# Hat.net
KiCad netlist of a schematic drawn in Altium Designer
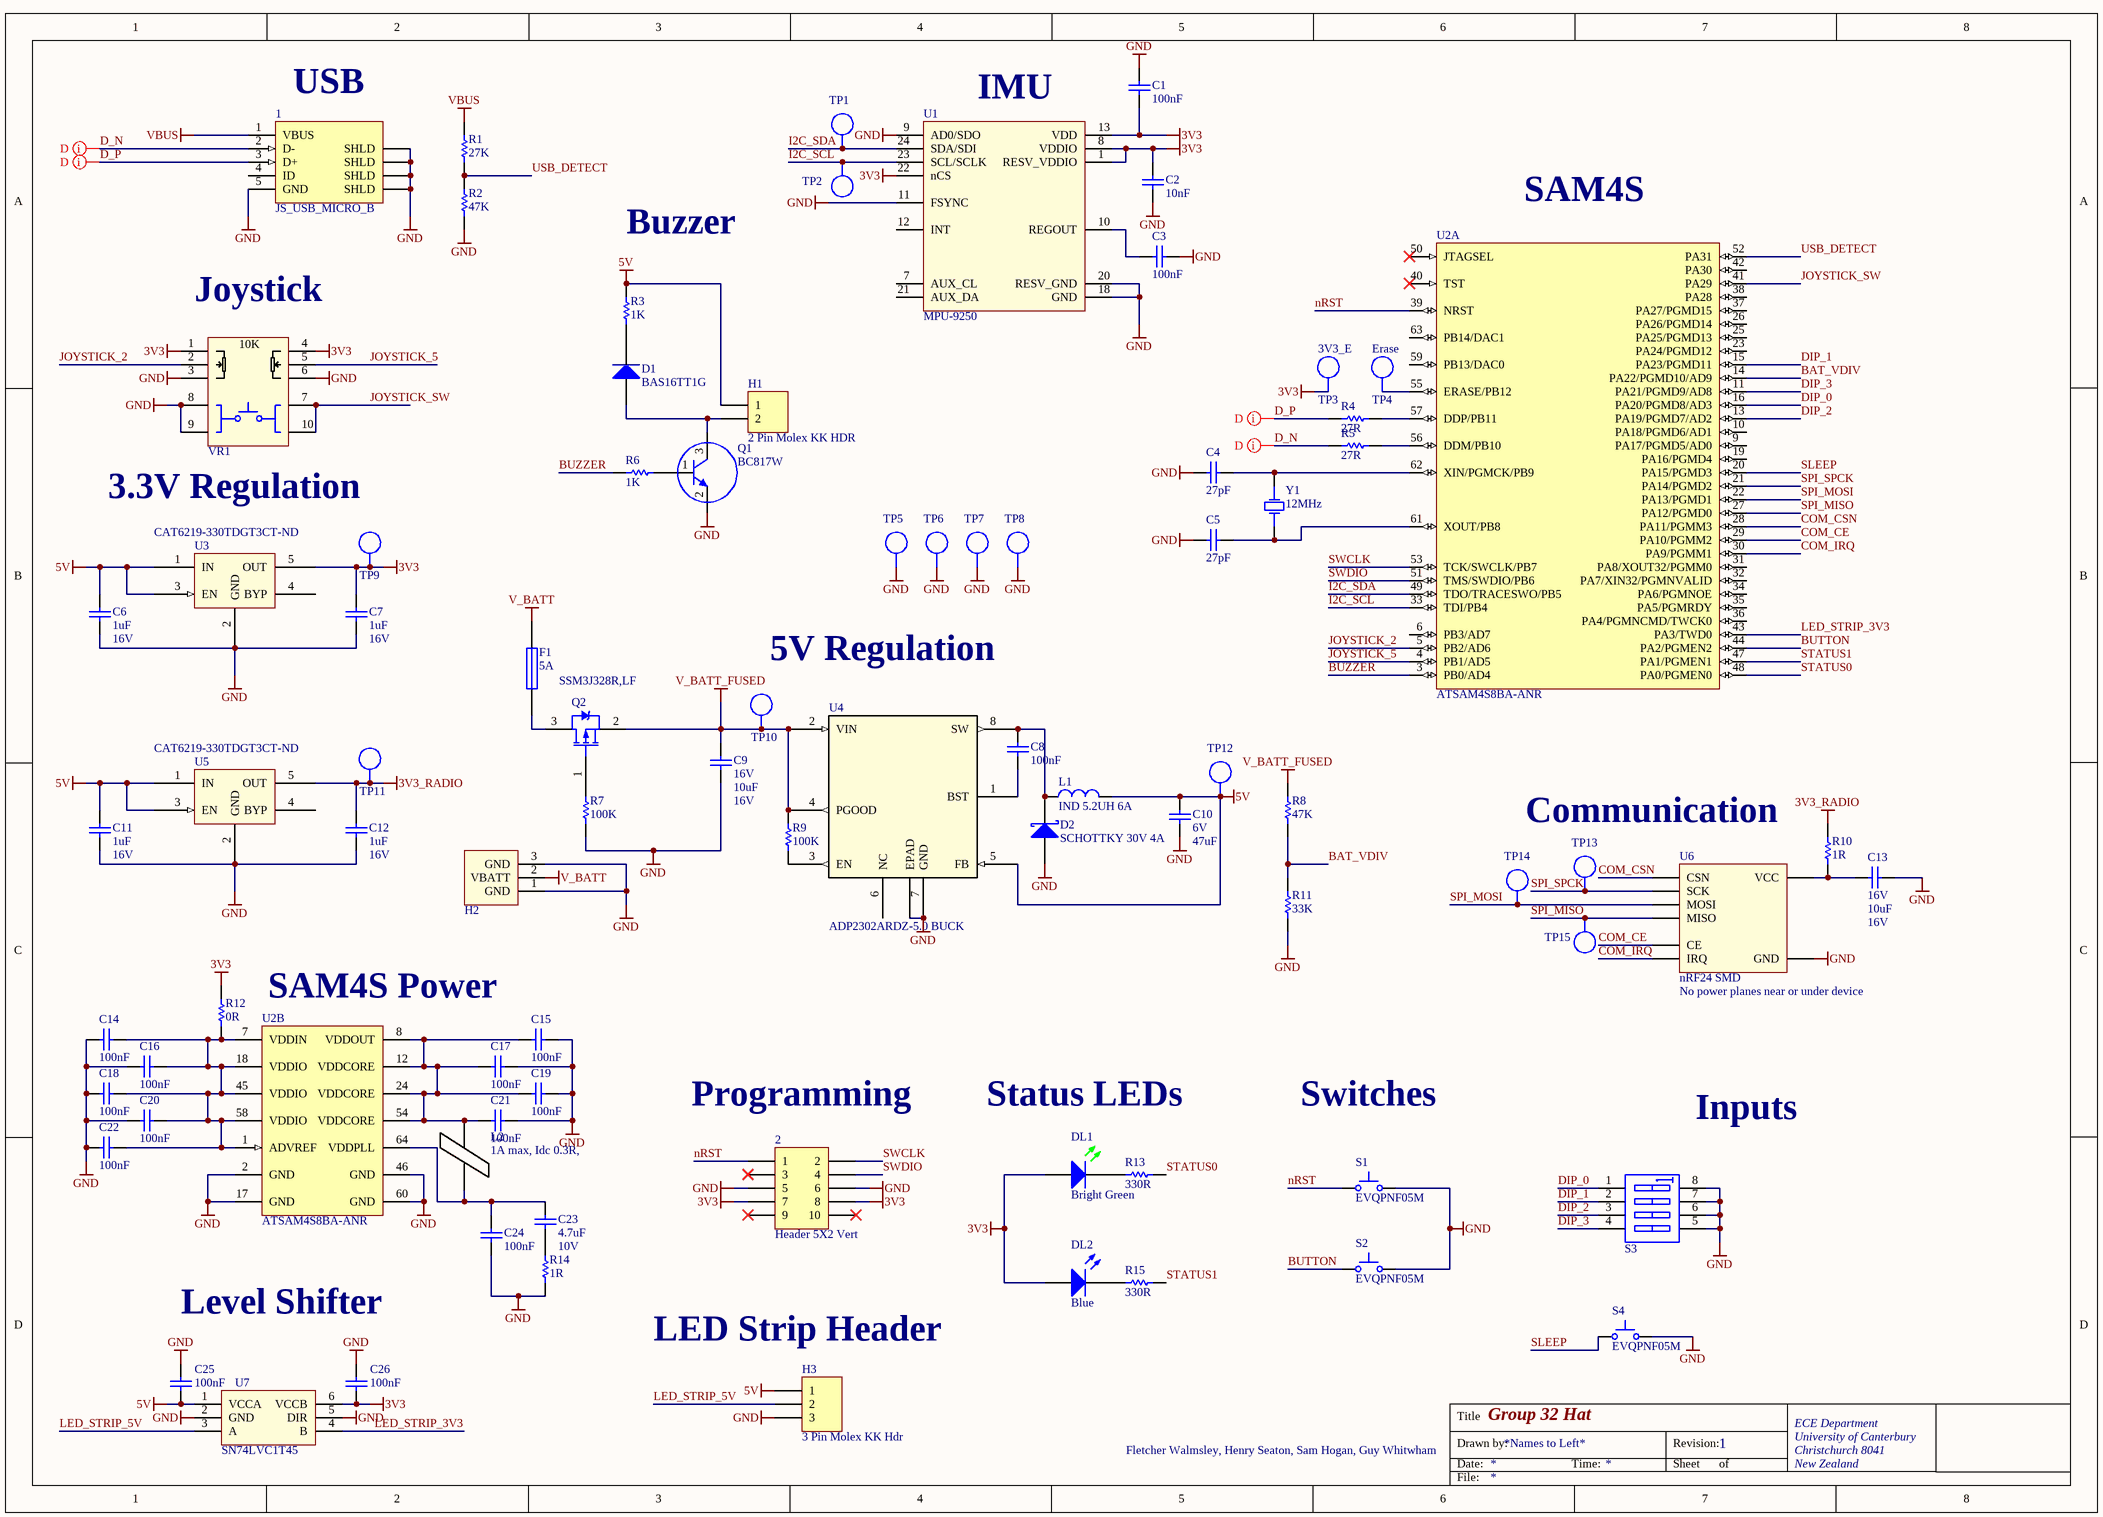
[diagram p0: Hat.SchDoc]

(export (version "E")
  (design (tool "Eeschema 10.0.6"))
  (components
    (comp (ref "1")
      (value "JS_USB_MICRO_B")
      (footprint "FCI_USB_10118194-0001LF")
      (description "CONN USB MICRO B RECPT SMT R/A")
      (fields (field (name "MANUFACTURER") "FCI") (field (name "MANUFACTURER PART NUMBER") "10118194-0001LF"))
      (libsource (lib "ECE AD19Components_19V1") (part "JS_USB_MICRO_B_SMT"))
    )
    (comp (ref "2")
      (value "Header 5X2 Vert")
      (footprint "IDC2.54-V10D")
      (description "IDC Header, 2,54mm, 10-Pin, Vert")
      (libsource (lib "ECE AD19Components_19V1") (part "JA_HDR_IDC_5X2_VERT"))
    )
    (comp (ref "C1")
      (value "100nF")
      (footprint "CAPC1608L")
      (description "CAP CER 100nF X7R +-10% 50V 0603")
      (libsource (lib "ECE AD19Components_19V1") (part "CC_100nF_0603"))
    )
    (comp (ref "C2")
      (value "10nF")
      (footprint "CAPC1608L")
      (description "CAP CER 10nF X7R +-10% 50V 0603")
      (libsource (lib "ECE AD19Components_19V1") (part "CC_10nF_0603"))
    )
    (comp (ref "C3")
      (value "100nF")
      (footprint "CAPC1608L")
      (description "CAP CER 100nF X7R +-10% 50V 0603")
      (libsource (lib "ECE AD19Components_19V1") (part "CC_100nF_0603"))
    )
    (comp (ref "C4")
      (value "27pF")
      (footprint "CAPC1608L")
      (description "CAP CER 27pF NPO/COG +-5% 50V 0603")
      (libsource (lib "ECE AD19Components_19V1") (part "CC_27pF_0603"))
    )
    (comp (ref "C5")
      (value "27pF")
      (footprint "CAPC1608L")
      (description "CAP CER 27pF NPO/COG +-5% 50V 0603")
      (libsource (lib "ECE AD19Components_19V1") (part "CC_27pF_0603"))
    )
    (comp (ref "C6")
      (value "1uF")
      (footprint "CAPC1608L")
      (description "CAP CER 1uF Y5V -20% +80% 16V 0603")
      (fields (field (name "MAX VOLTAGE") "16V"))
      (libsource (lib "ECE AD19Components_19V1") (part "CC_1uF_0603"))
    )
    (comp (ref "C7")
      (value "1uF")
      (footprint "CAPC1608L")
      (description "CAP CER 1uF Y5V -20% +80% 16V 0603")
      (fields (field (name "MAX VOLTAGE") "16V"))
      (libsource (lib "ECE AD19Components_19V1") (part "CC_1uF_0603"))
    )
    (comp (ref "C8")
      (value "100nF")
      (footprint "CAPC1608L")
      (description "CAP CER 100nF X7R +-10% 50V 0603")
      (libsource (lib "ECE AD19Components_19V1") (part "CC_100nF_0603"))
    )
    (comp (ref "C9")
      (value "10uF")
      (footprint "CAPC2012L")
      (description "CAP CER 10uF X5R 16V 0805")
      (fields
        (field (name "MANUFACTURER") "Samsung Electro-Mechanics")
        (field (name "MANUFACTURER PART NUMBER") "CL21A106KOQNNWE")
        (field (name "VOLTAGE - RATED") "16V")
        (field (name "MAX VOLTAGE") "16V")
      )
      (libsource (lib "ENCE461AD19_19V2") (part "CC_10uF_16V_0805"))
    )
    (comp (ref "C10")
      (value "47uF")
      (footprint "CAPC3216L")
      (description "CAP CER 47uF X5R -/+20% 6V 1206")
      (fields (field (name "MAX VOLTAGE") "6V"))
      (libsource (lib "ECE AD19Components_19V1") (part "CC_47uF_1206"))
    )
    (comp (ref "C11")
      (value "1uF")
      (footprint "CAPC1608L")
      (description "CAP CER 1uF Y5V -20% +80% 16V 0603")
      (fields (field (name "MAX VOLTAGE") "16V"))
      (libsource (lib "ECE AD19Components_19V1") (part "CC_1uF_0603"))
    )
    (comp (ref "C12")
      (value "1uF")
      (footprint "CAPC1608L")
      (description "CAP CER 1uF Y5V -20% +80% 16V 0603")
      (fields (field (name "MAX VOLTAGE") "16V"))
      (libsource (lib "ECE AD19Components_19V1") (part "CC_1uF_0603"))
    )
    (comp (ref "C13")
      (value "10uF")
      (footprint "CAPC2012L")
      (description "CAP CER 10uF X5R 16V 0805")
      (fields
        (field (name "MANUFACTURER") "Samsung Electro-Mechanics")
        (field (name "MANUFACTURER PART NUMBER") "CL21A106KOQNNWE")
        (field (name "VOLTAGE - RATED") "16V")
        (field (name "MAX VOLTAGE") "16V")
      )
      (libsource (lib "ENCE461AD19_19V2") (part "CC_10uF_16V_0805"))
    )
    (comp (ref "C14")
      (value "100nF")
      (footprint "CAPC1608L")
      (description "CAP CER 100nF X7R +-10% 50V 0603")
      (libsource (lib "ECE AD19Components_19V1") (part "CC_100nF_0603"))
    )
    (comp (ref "C15")
      (value "100nF")
      (footprint "CAPC1608L")
      (description "CAP CER 100nF X7R +-10% 50V 0603")
      (libsource (lib "ECE AD19Components_19V1") (part "CC_100nF_0603"))
    )
    (comp (ref "C16")
      (value "100nF")
      (footprint "CAPC1608L")
      (description "CAP CER 100nF X7R +-10% 50V 0603")
      (libsource (lib "ECE AD19Components_19V1") (part "CC_100nF_0603"))
    )
    (comp (ref "C17")
      (value "100nF")
      (footprint "CAPC1608L")
      (description "CAP CER 100nF X7R +-10% 50V 0603")
      (libsource (lib "ECE AD19Components_19V1") (part "CC_100nF_0603"))
    )
    (comp (ref "C18")
      (value "100nF")
      (footprint "CAPC1608L")
      (description "CAP CER 100nF X7R +-10% 50V 0603")
      (libsource (lib "ECE AD19Components_19V1") (part "CC_100nF_0603"))
    )
    (comp (ref "C19")
      (value "100nF")
      (footprint "CAPC1608L")
      (description "CAP CER 100nF X7R +-10% 50V 0603")
      (libsource (lib "ECE AD19Components_19V1") (part "CC_100nF_0603"))
    )
    (comp (ref "C20")
      (value "100nF")
      (footprint "CAPC1608L")
      (description "CAP CER 100nF X7R +-10% 50V 0603")
      (libsource (lib "ECE AD19Components_19V1") (part "CC_100nF_0603"))
    )
    (comp (ref "C21")
      (value "100nF")
      (footprint "CAPC1608L")
      (description "CAP CER 100nF X7R +-10% 50V 0603")
      (libsource (lib "ECE AD19Components_19V1") (part "CC_100nF_0603"))
    )
    (comp (ref "C22")
      (value "100nF")
      (footprint "CAPC1608L")
      (description "CAP CER 100nF X7R +-10% 50V 0603")
      (libsource (lib "ECE AD19Components_19V1") (part "CC_100nF_0603"))
    )
    (comp (ref "C23")
      (value "4.7uF")
      (footprint "CAPC1608N")
      (description "CAP CER 4.7uF X5R +-20%  10V 0603")
      (fields (field (name "MAX VOLTAGE") "10V"))
      (libsource (lib "ECE AD19Components_19V1") (part "CC_4.7uF_0603"))
    )
    (comp (ref "C24")
      (value "100nF")
      (footprint "CAPC1608L")
      (description "CAP CER 100nF X7R +-10% 50V 0603")
      (libsource (lib "ECE AD19Components_19V1") (part "CC_100nF_0603"))
    )
    (comp (ref "C25")
      (value "100nF")
      (footprint "CAPC1608L")
      (description "CAP CER 100nF X7R +-10% 50V 0603")
      (libsource (lib "ECE AD19Components_19V1") (part "CC_100nF_0603"))
    )
    (comp (ref "C26")
      (value "100nF")
      (footprint "CAPC1608L")
      (description "CAP CER 100nF X7R +-10% 50V 0603")
      (libsource (lib "ECE AD19Components_19V1") (part "CC_100nF_0603"))
    )
    (comp (ref "D1")
      (value "BAS16TT1G")
      (footprint "SOT416")
      (description "Diode Switching, Vr 75V, 200mA, SOT-416")
      (fields (field (name "MANUFACTURER") "ON Semiconductor"))
      (libsource (lib "ECE AD19Components_19V1") (part "DR_BAS16TT1G"))
    )
    (comp (ref "D2")
      (value "SCHOTTKY 30V 4A")
      (footprint "SMC")
      (description "DIODE SCHOTTKY 30V 4A SMC")
      (fields
        (field (name "MANUFACTURER") "ON Semiconductor")
        (field (name "MANUFACTURER PART NUMBER") "MBRS330T3G")
      )
      (libsource (lib "ENCE461AD19_19V2") (part "MBRS330T3G"))
    )
    (comp (ref "DL1")
      (value "Bright Green")
      (footprint "WL-SMCW0603")
      (description "LED Bright Green 40mcd 0603 SMD")
      (fields
        (field (name "MANUFACTURER") "WURTH ELEKTRONIK")
        (field (name "MANUFACTURER PART NUMBER") "150060VS75000")
        (field (name "LED COLOUR") "Bright Green")
      )
      (libsource (lib "ECE AD19Components_19V1") (part "DL_150060VS75000"))
    )
    (comp (ref "DL2")
      (value "Blue")
      (footprint "WL-SMCW0603")
      (description "LED Blue 270mcd 0603 SMD")
      (fields
        (field (name "MANUFACTURER") "WURTH ELEKTRONIK")
        (field (name "MANUFACTURER PART NUMBER") "150060BS75000")
        (field (name "LED COLOUR") "Blue")
      )
      (libsource (lib "ECE AD19Components_19V1") (part "DL_150060BS75000"))
    )
    (comp (ref "F1")
      (value "5A")
      (footprint "RESC3216N")
      (description "Fuse 5.0A Fast Acting 1206 SMD")
      (fields (field (name "MANUFACTURER PART NUMBER") "C1F5") (field (name "MANUFACTURER") "Bel TRP"))
      (libsource (lib "ECE AD19Components_19V1") (part "FS_Fuse_5.0A"))
    )
    (comp (ref "H1")
      (value "2 Pin Molex KK HDR")
      (footprint "MOLEX_KK_2_HDR")
      (description "CONN HEADER 2POS 2.54mm VERT_Thru Hole")
      (libsource (lib "ECE AD19Components_19V1") (part "JA_MOLEX_KK_2POS"))
    )
    (comp (ref "H2")
      (value "Battery_HEADER_3pin")
      (footprint "BATT_HEADER_3POS")
      (description "3Pin Header 2.54mm spacing")
      (libsource (lib "ENCE461AD19_19V2") (part "Battery_HEADER_3pin"))
    )
    (comp (ref "H3")
      (value "3 Pin Molex KK Hdr")
      (footprint "MOLEX_KK_3_HDR")
      (description "CONN HEADER 3POS 2.54mm VERT_Thru Hole")
      (fields (field (name "MANUFACTURER") "Molex"))
      (libsource (lib "ECE AD19Components_19V1") (part "JA_MOLEX_KK_3POS"))
    )
    (comp (ref "L1")
      (value "IND 5.2UH 6A")
      (footprint "INDUCTOR5u2")
      (description "FIXED IND 5.2UH 6A 22 MOHM SMD")
      (fields
        (field (name "MANUFACTURER") "Sumida America Components Inc.")
        (field (name "MANUFACTURER PART NUMBER") "CDRH104RNP-5R2NC")
      )
      (libsource (lib "ENCE461AD19_19V2") (part "CDRH104RNP-5R2NC"))
    )
    (comp (ref "L2")
      (value "1A max, Idc 0.3R,")
      (footprint "INDC3216L")
      (description "Ferrite Bead, Rdc 0.3R, Z100MHZ 600R, Imax 1A, SMD 1206")
      (fields
        (field (name "MANUFACTURER") "FAIR-RITE")
        (field (name "MANUFACTURER PART NUMBER") "2512066017Y1")
      )
      (libsource (lib "ECE AD19Components_19V1") (part "IN_Ferrite-Bead"))
    )
    (comp (ref "Q1")
      (value "BC817W")
      (footprint "SOT323_M")
      (description "NPN GP Bipolar Transistor 45V 500mA SOT323")
      (fields (field (name "MANUFACTURER") "NXP"))
      (libsource (lib "ECE AD19Components_19V1") (part "TB_BC817W"))
    )
    (comp (ref "Q2")
      (value "SSM3J328R,LF")
      (footprint "SOT23_L")
      (description "MOSFET P-CH 20V 6A SOT23-3")
      (fields
        (field (name "MANUFACTURER") "Toshiba")
        (field (name "MANUFACTURER PART NUMBER") "SSM3J328R,LF")
      )
      (libsource (lib "ECE AD19Components_19V1") (part "TM_SSM3J328R"))
    )
    (comp (ref "R1")
      (value "27K")
      (footprint "RESC1608L")
      (description "RES 27K OHM 1/10W 5% 0603 SMD")
      (libsource (lib "ECE AD19Components_19V1") (part "RS_27K"))
    )
    (comp (ref "R2")
      (value "47K")
      (footprint "RESC1608N")
      (description "RES 47.0K OHM 1/10W 5% 0603 SMD")
      (libsource (lib "ECE AD19Components_19V1") (part "RS_47K"))
    )
    (comp (ref "R3")
      (value "1K")
      (footprint "RESC1608L")
      (description "RES 1.0K OHM 1/10W 5% 0603 SMD")
      (libsource (lib "ECE AD19Components_19V1") (part "RS_1K"))
    )
    (comp (ref "R4")
      (value "27R")
      (footprint "RESC1608L")
      (description "RES 27 OHM 1/10W 5% 0603 SMD")
      (libsource (lib "ECE AD19Components_19V1") (part "RS_27R"))
    )
    (comp (ref "R5")
      (value "27R")
      (footprint "RESC1608L")
      (description "RES 27 OHM 1/10W 5% 0603 SMD")
      (libsource (lib "ECE AD19Components_19V1") (part "RS_27R"))
    )
    (comp (ref "R6")
      (value "1K")
      (footprint "RESC1608L")
      (description "RES 1.0K OHM 1/10W 5% 0603 SMD")
      (libsource (lib "ECE AD19Components_19V1") (part "RS_1K"))
    )
    (comp (ref "R7")
      (value "100K")
      (footprint "RESC1608L")
      (description "RES 100K OHM 1/10W 5% 0603 SMD")
      (libsource (lib "ECE AD19Components_19V1") (part "RS_100K"))
    )
    (comp (ref "R8")
      (value "47K")
      (footprint "RESC1608N")
      (description "RES 47.0K OHM 1/10W 5% 0603 SMD")
      (libsource (lib "ECE AD19Components_19V1") (part "RS_47K"))
    )
    (comp (ref "R9")
      (value "100K")
      (footprint "RESC1608L")
      (description "RES 100K OHM 1/10W 5% 0603 SMD")
      (libsource (lib "ECE AD19Components_19V1") (part "RS_100K"))
    )
    (comp (ref "R10")
      (value "1R")
      (footprint "RESC3216L")
      (description "RES 1R OHM 1/4W 5% 1206 SMD")
      (libsource (lib "ECE AD19Components_19V1") (part "RT_1R"))
    )
    (comp (ref "R11")
      (value "33K")
      (footprint "RESC1608L")
      (description "RES 33.0K OHM 1/10W 5% 0603 SMD")
      (libsource (lib "ECE AD19Components_19V1") (part "RS_33K"))
    )
    (comp (ref "R12")
      (value "0R")
      (footprint "RESC1608L")
      (description "RES 0.0 OHM 1/10W 5% 0603 SMD")
      (libsource (lib "ECE AD19Components_19V1") (part "RS_0R0"))
    )
    (comp (ref "R13")
      (value "330R")
      (footprint "RESC1608L")
      (description "RES 330 OHM 1/10W 5% 0603 SMD")
      (libsource (lib "ECE AD19Components_19V1") (part "RS_330R"))
    )
    (comp (ref "R14")
      (value "1R")
      (footprint "RESC3216L")
      (description "RES 1R OHM 1/4W 5% 1206 SMD")
      (libsource (lib "ECE AD19Components_19V1") (part "RT_1R"))
    )
    (comp (ref "R15")
      (value "330R")
      (footprint "RESC1608L")
      (description "RES 330 OHM 1/10W 5% 0603 SMD")
      (libsource (lib "ECE AD19Components_19V1") (part "RS_330R"))
    )
    (comp (ref "S1")
      (value "EVQPNF05M")
      (footprint "EVQPNF05M")
      (description "Panasonic 6 x 3.5mm SMD Light Touch Switch Type SMD")
      (fields (field (name "MANUFACTURER") "Panasonic"))
      (libsource (lib "ENCE461_extras_2020") (part "WS_EVQPNF05M"))
    )
    (comp (ref "S2")
      (value "EVQPNF05M")
      (footprint "EVQPNF05M")
      (description "Panasonic 6 x 3.5mm SMD Light Touch Switch Type SMD")
      (fields (field (name "MANUFACTURER") "Panasonic"))
      (libsource (lib "ECE AD19Components_19V1") (part "WS_EVQPNF05M"))
    )
    (comp (ref "S3")
      (value "WS_SW DIP-4")
      (footprint "DIP_SW_4WAY_SMD -")
      (description "DIP Switch, 4 Position, SPST SMD")
      (fields
        (field (name "MANUFACTURER") "OMRON ELECTRONIC COMPONENTS")
        (field (name "MANUFACTURER PART NUMBER") "A6SN-4101")
      )
      (libsource (lib "ECE AD19Components_19V1") (part "WS_SW DIP-4"))
    )
    (comp (ref "S4")
      (value "EVQPNF05M")
      (footprint "EVQPNF05M")
      (description "Panasonic 6 x 3.5mm SMD Light Touch Switch Type SMD")
      (fields (field (name "MANUFACTURER") "Panasonic"))
      (libsource (lib "ECE AD19Components_19V1") (part "WS_EVQPNF05M"))
    )
    (comp (ref "TP1")
      (value "SDA")
      (footprint "TP_1206")
      (description "Test-Point 3.3x1.6x2.1mm SMD")
      (fields
        (field (name "MANUFACTURER") "Harwin Inc")
        (field (name "MANUFACTURER PART NUMBER") "S1751-46R")
      )
      (libsource (lib "ECE AD19Components_19V1") (part "TP_1206"))
    )
    (comp (ref "TP2")
      (value "SCK")
      (footprint "TP_1206")
      (description "Test-Point 3.3x1.6x2.1mm SMD")
      (fields
        (field (name "MANUFACTURER") "Harwin Inc")
        (field (name "MANUFACTURER PART NUMBER") "S1751-46R")
      )
      (libsource (lib "ECE AD19Components_19V1") (part "TP_1206"))
    )
    (comp (ref "TP3")
      (value "3V3_E")
      (footprint "TP_1206")
      (description "Test-Point 3.3x1.6x2.1mm SMD")
      (fields
        (field (name "MANUFACTURER") "Harwin Inc")
        (field (name "MANUFACTURER PART NUMBER") "S1751-46R")
      )
      (libsource (lib "ECE AD19Components_19V1") (part "TP_1206"))
    )
    (comp (ref "TP4")
      (value "Erase")
      (footprint "TP_1206")
      (description "Test-Point 3.3x1.6x2.1mm SMD")
      (fields
        (field (name "MANUFACTURER") "Harwin Inc")
        (field (name "MANUFACTURER PART NUMBER") "S1751-46R")
      )
      (libsource (lib "ECE AD19Components_19V1") (part "TP_1206"))
    )
    (comp (ref "TP5")
      (value "GND")
      (footprint "TP_1206")
      (description "Test-Point 3.3x1.6x2.1mm SMD")
      (fields
        (field (name "MANUFACTURER") "Harwin Inc")
        (field (name "MANUFACTURER PART NUMBER") "S1751-46R")
      )
      (libsource (lib "ECE AD19Components_19V1") (part "TP_1206"))
    )
    (comp (ref "TP6")
      (value "GND")
      (footprint "TP_1206")
      (description "Test-Point 3.3x1.6x2.1mm SMD")
      (fields
        (field (name "MANUFACTURER") "Harwin Inc")
        (field (name "MANUFACTURER PART NUMBER") "S1751-46R")
      )
      (libsource (lib "ECE AD19Components_19V1") (part "TP_1206"))
    )
    (comp (ref "TP7")
      (value "GND")
      (footprint "TP_1206")
      (description "Test-Point 3.3x1.6x2.1mm SMD")
      (fields
        (field (name "MANUFACTURER") "Harwin Inc")
        (field (name "MANUFACTURER PART NUMBER") "S1751-46R")
      )
      (libsource (lib "ECE AD19Components_19V1") (part "TP_1206"))
    )
    (comp (ref "TP8")
      (value "GND")
      (footprint "TP_1206")
      (description "Test-Point 3.3x1.6x2.1mm SMD")
      (fields
        (field (name "MANUFACTURER") "Harwin Inc")
        (field (name "MANUFACTURER PART NUMBER") "S1751-46R")
      )
      (libsource (lib "ECE AD19Components_19V1") (part "TP_1206"))
    )
    (comp (ref "TP9")
      (value "3V3")
      (footprint "TP_1206")
      (description "Test-Point 3.3x1.6x2.1mm SMD")
      (fields
        (field (name "MANUFACTURER") "Harwin Inc")
        (field (name "MANUFACTURER PART NUMBER") "S1751-46R")
      )
      (libsource (lib "ECE AD19Components_19V1") (part "TP_1206"))
    )
    (comp (ref "TP10")
      (value "V_BATT")
      (footprint "TP_1206")
      (description "Test-Point 3.3x1.6x2.1mm SMD")
      (fields
        (field (name "MANUFACTURER") "Harwin Inc")
        (field (name "MANUFACTURER PART NUMBER") "S1751-46R")
      )
      (libsource (lib "ECE AD19Components_19V1") (part "TP_1206"))
    )
    (comp (ref "TP11")
      (value "3V3_R")
      (footprint "TP_1206")
      (description "Test-Point 3.3x1.6x2.1mm SMD")
      (fields
        (field (name "MANUFACTURER") "Harwin Inc")
        (field (name "MANUFACTURER PART NUMBER") "S1751-46R")
      )
      (libsource (lib "ECE AD19Components_19V1") (part "TP_1206"))
    )
    (comp (ref "TP12")
      (value "5V")
      (footprint "TP_1206")
      (description "Test-Point 3.3x1.6x2.1mm SMD")
      (fields
        (field (name "MANUFACTURER") "Harwin Inc")
        (field (name "MANUFACTURER PART NUMBER") "S1751-46R")
      )
      (libsource (lib "ECE AD19Components_19V1") (part "TP_1206"))
    )
    (comp (ref "TP13")
      (value "SPCK")
      (footprint "TP_1206")
      (description "Test-Point 3.3x1.6x2.1mm SMD")
      (fields
        (field (name "MANUFACTURER") "Harwin Inc")
        (field (name "MANUFACTURER PART NUMBER") "S1751-46R")
      )
      (libsource (lib "ECE AD19Components_19V1") (part "TP_1206"))
    )
    (comp (ref "TP14")
      (value "MOSI")
      (footprint "TP_1206")
      (description "Test-Point 3.3x1.6x2.1mm SMD")
      (fields
        (field (name "MANUFACTURER") "Harwin Inc")
        (field (name "MANUFACTURER PART NUMBER") "S1751-46R")
      )
      (libsource (lib "ECE AD19Components_19V1") (part "TP_1206"))
    )
    (comp (ref "TP15")
      (value "MISO")
      (footprint "TP_1206")
      (description "Test-Point 3.3x1.6x2.1mm SMD")
      (fields
        (field (name "MANUFACTURER") "Harwin Inc")
        (field (name "MANUFACTURER PART NUMBER") "S1751-46R")
      )
      (libsource (lib "ECE AD19Components_19V1") (part "TP_1206"))
    )
    (comp (ref "U1")
      (value "MPU-9250")
      (footprint "Quad24")
      (description "9 axis IMU")
      (libsource (lib "ENCE461AD19_19V2") (part "MPU-9250"))
    )
    (comp (ref "U2")
      (value "ATSAM4S8BA-ANR")
      (footprint "LQFP64_L")
      (description "IC MCU 32BIT 512KB FLASH 64LQFP")
      (fields (field (name "MANUFACTURER") "Atmel"))
      (libsource (lib "ECE AD19Components_19V1") (part "SE_ATSAM4S16BA-MU"))
    )
    (comp (ref "U3")
      (value "CAT6219-330TDGT3")
      (footprint "SOT95P280X145-5N")
      (description "IC REG LIN 3.3V 500MA TSOT23-5")
      (fields
        (field (name "BASE PART NUMBER") "CAT6219")
        (field (name "SUPPLIER PART NUMBER") "CAT6219-330TDGT3CT-ND")
      )
      (libsource (lib "ENCE461AD19_19V2") (part "SV_CAT6219-330TDGT3"))
    )
    (comp (ref "U4")
      (value "ADP2302ARDZ-5.0 BUCK")
      (footprint "RD_8_1")
      (description "IC REG BUCK 5V 2A 8SOIC")
      (fields (field (name "MANUFACTURER_PART_NUMBER") "ADP2302ARDZ-5.0-R7"))
      (libsource (lib "ENCE461AD19_19V2") (part "ADP2302ARDZ-5.0-R7"))
    )
    (comp (ref "U5")
      (value "CAT6219-330TDGT3")
      (footprint "SOT95P280X145-5N")
      (description "IC REG LIN 3.3V 500MA TSOT23-5")
      (fields
        (field (name "BASE PART NUMBER") "CAT6219")
        (field (name "SUPPLIER PART NUMBER") "CAT6219-330TDGT3CT-ND")
      )
      (libsource (lib "ENCE461AD19_19V2") (part "SV_CAT6219-330TDGT3"))
    )
    (comp (ref "U6")
      (value "nRF24 SMD")
      (footprint "NRF24")
      (description "nRF24 SMD Module")
      (fields (field (name "WARNING") "No power planes near or under device"))
      (libsource (lib "ENCE461AD19_19V2") (part "NRF24"))
    )
    (comp (ref "U7")
      (value "SN74LVC1T45")
      (footprint "SOT23-6_N")
      (description "1.8V - 5V level converter")
      (libsource (lib "ENCE461_extras_2020") (part "SN74LVC1T45"))
    )
    (comp (ref "VR1")
      (value "Joystick 10k with Sw")
      (footprint "Joystick_Sw")
      (description "JOYSTICK 10K OHM 2 AXIS TH")
      (libsource (lib "ENCE461AD19_19V2") (part "Joystick 10k with Sw"))
    )
    (comp (ref "Y1")
      (value "12MHz")
      (footprint "6.0X3.5-4")
      (description "CRYSTAL 12MHZ 18PF 6X3.5mm SMD")
      (fields
        (field (name "MANUFACTURER") "CTS-Frequency Controls")
        (field (name "MANUFACTURER PART NUMBER") "406C35D12M00000")
        (field (name "FREQUENCY") "12MHz")
      )
      (libsource (lib "ECE AD19Components_19V1") (part "XT_CRYSTAL_12MHz_18pF"))
    )
  )
  (nets
    (net (code "1") (name "/BAT_VDIV") (class "Default")
      (node (ref "R11") (pin "1") (pinfunction "1_1") (pintype "passive"))
      (node (ref "R8") (pin "2") (pinfunction "2_2") (pintype "passive"))
      (node (ref "U2") (pin "14") (pinfunction "PA22/PGMD10/AD9_14") (pintype "bidirectional"))
    )
    (net (code "2") (name "/BUTTON") (class "Default")
      (node (ref "S2") (pin "1") (pintype "passive"))
      (node (ref "U2") (pin "44") (pinfunction "PA2/PGMEN2_44") (pintype "bidirectional"))
    )
    (net (code "3") (name "/BUZZER") (class "Default")
      (node (ref "R6") (pin "2") (pinfunction "2_2") (pintype "passive"))
      (node (ref "U2") (pin "3") (pinfunction "PB0/AD4_3") (pintype "bidirectional"))
    )
    (net (code "4") (name "/COM_CE") (class "Default")
      (node (ref "U2") (pin "29") (pinfunction "PA10/PGMM2_29") (pintype "bidirectional"))
      (node (ref "U6") (pin "3") (pinfunction "CE_3") (pintype "passive"))
    )
    (net (code "5") (name "/COM_CSN") (class "Default")
      (node (ref "U2") (pin "28") (pinfunction "PA11/PGMM3_28") (pintype "bidirectional"))
      (node (ref "U6") (pin "4") (pinfunction "CSN_4") (pintype "passive"))
    )
    (net (code "6") (name "/COM_IRQ") (class "Default")
      (node (ref "U2") (pin "30") (pinfunction "PA9/PGMM1_30") (pintype "bidirectional"))
      (node (ref "U6") (pin "8") (pinfunction "IRQ_8") (pintype "passive"))
    )
    (net (code "7") (name "/DIP_0") (class "Default")
      (node (ref "S3") (pin "1") (pinfunction "A1_1") (pintype "passive"))
      (node (ref "U2") (pin "16") (pinfunction "PA20/PGMD8/AD3_16") (pintype "bidirectional"))
    )
    (net (code "8") (name "/DIP_1") (class "Default")
      (node (ref "S3") (pin "2") (pinfunction "A2_2") (pintype "passive"))
      (node (ref "U2") (pin "15") (pinfunction "PA23/PGMD11_15") (pintype "bidirectional"))
    )
    (net (code "9") (name "/DIP_2") (class "Default")
      (node (ref "S3") (pin "3") (pinfunction "A3_3") (pintype "passive"))
      (node (ref "U2") (pin "13") (pinfunction "PA19/PGMD7/AD2_13") (pintype "bidirectional"))
    )
    (net (code "10") (name "/DIP_3") (class "Default")
      (node (ref "S3") (pin "4") (pinfunction "A4_4") (pintype "passive"))
      (node (ref "U2") (pin "11") (pinfunction "PA21/PGMD9/AD8_11") (pintype "bidirectional"))
    )
    (net (code "11") (name "/D_N") (class "Default")
      (node (ref "1") (pin "2") (pinfunction "D-_2") (pintype "input"))
      (node (ref "R5") (pin "1") (pinfunction "1_1") (pintype "passive"))
    )
    (net (code "12") (name "/D_P") (class "Default")
      (node (ref "1") (pin "3") (pinfunction "D+_3") (pintype "input"))
      (node (ref "R4") (pin "1") (pinfunction "1_1") (pintype "passive"))
    )
    (net (code "13") (name "/I2C_SCL") (class "Default")
      (node (ref "TP2") (pin "1") (pinfunction "1_1") (pintype "passive"))
      (node (ref "U1") (pin "23") (pinfunction "SCL/SCLK_23") (pintype "passive"))
      (node (ref "U2") (pin "33") (pinfunction "TDI/PB4_33") (pintype "bidirectional"))
    )
    (net (code "14") (name "/I2C_SDA") (class "Default")
      (node (ref "TP1") (pin "1") (pinfunction "1_1") (pintype "passive"))
      (node (ref "U1") (pin "24") (pinfunction "SDA/SDI_24") (pintype "passive"))
      (node (ref "U2") (pin "49") (pinfunction "TDO/TRACESWO/PB5_49") (pintype "bidirectional"))
    )
    (net (code "15") (name "/JOYSTICK_2") (class "Default")
      (node (ref "U2") (pin "5") (pinfunction "PB2/AD6_5") (pintype "bidirectional"))
      (node (ref "VR1") (pin "2") (pinfunction "2_2") (pintype "passive"))
    )
    (net (code "16") (name "/JOYSTICK_5") (class "Default")
      (node (ref "U2") (pin "4") (pinfunction "PB1/AD5_4") (pintype "bidirectional"))
      (node (ref "VR1") (pin "5") (pinfunction "2'_5") (pintype "passive"))
    )
    (net (code "17") (name "/JOYSTICK_SW") (class "Default")
      (node (ref "U2") (pin "41") (pinfunction "PA29_41") (pintype "bidirectional"))
      (node (ref "VR1") (pin "10") (pinfunction "10_10") (pintype "passive"))
      (node (ref "VR1") (pin "7") (pinfunction "7_7") (pintype "passive"))
    )
    (net (code "18") (name "/LED_STRIP_3V3") (class "Default")
      (node (ref "U2") (pin "43") (pinfunction "PA3/TWD0_43") (pintype "bidirectional"))
      (node (ref "U7") (pin "4") (pinfunction "B_4") (pintype "passive"))
    )
    (net (code "19") (name "/LED_STRIP_5V") (class "Default")
      (node (ref "H3") (pin "2") (pinfunction "2_2") (pintype "passive"))
      (node (ref "U7") (pin "3") (pinfunction "A_3") (pintype "passive"))
    )
    (net (code "20") (name "/SLEEP") (class "Default")
      (node (ref "S4") (pin "1") (pintype "passive"))
      (node (ref "U2") (pin "20") (pinfunction "PA15/PGMD3_20") (pintype "bidirectional"))
    )
    (net (code "21") (name "/SPI_MISO") (class "Default")
      (node (ref "TP15") (pin "1") (pinfunction "1_1") (pintype "passive"))
      (node (ref "U2") (pin "27") (pinfunction "PA12/PGMD0_27") (pintype "bidirectional"))
      (node (ref "U6") (pin "7") (pinfunction "MISO_7") (pintype "passive"))
    )
    (net (code "22") (name "/SPI_MOSI") (class "Default")
      (node (ref "TP14") (pin "1") (pinfunction "1_1") (pintype "passive"))
      (node (ref "U2") (pin "22") (pinfunction "PA13/PGMD1_22") (pintype "bidirectional"))
      (node (ref "U6") (pin "6") (pinfunction "MOSI_6") (pintype "passive"))
    )
    (net (code "23") (name "/SPI_SPCK") (class "Default")
      (node (ref "TP13") (pin "1") (pinfunction "1_1") (pintype "passive"))
      (node (ref "U2") (pin "21") (pinfunction "PA14/PGMD2_21") (pintype "bidirectional"))
      (node (ref "U6") (pin "5") (pinfunction "SCK_5") (pintype "passive"))
    )
    (net (code "24") (name "/STATUS0") (class "Default")
      (node (ref "R13") (pin "2") (pinfunction "2_2") (pintype "passive"))
      (node (ref "U2") (pin "48") (pinfunction "PA0/PGMEN0_48") (pintype "bidirectional"))
    )
    (net (code "25") (name "/STATUS1") (class "Default")
      (node (ref "R15") (pin "2") (pinfunction "2_2") (pintype "passive"))
      (node (ref "U2") (pin "47") (pinfunction "PA1/PGMEN1_47") (pintype "bidirectional"))
    )
    (net (code "26") (name "/SWCLK") (class "Default")
      (node (ref "2") (pin "2") (pinfunction "2_2") (pintype "passive"))
      (node (ref "U2") (pin "53") (pinfunction "TCK/SWCLK/PB7_53") (pintype "bidirectional"))
    )
    (net (code "27") (name "/SWDIO") (class "Default")
      (node (ref "2") (pin "4") (pinfunction "4_4") (pintype "passive"))
      (node (ref "U2") (pin "51") (pinfunction "TMS/SWDIO/PB6_51") (pintype "bidirectional"))
    )
    (net (code "28") (name "/USB_DETECT") (class "Default")
      (node (ref "R1") (pin "1") (pinfunction "1_1") (pintype "passive"))
      (node (ref "R2") (pin "2") (pinfunction "2_2") (pintype "passive"))
      (node (ref "U2") (pin "52") (pinfunction "PA31_52") (pintype "bidirectional"))
    )
    (net (code "29") (name "/nRST") (class "Default")
      (node (ref "2") (pin "1") (pinfunction "1_1") (pintype "passive"))
      (node (ref "S1") (pin "1") (pintype "passive"))
      (node (ref "U2") (pin "39") (pinfunction "NRST_39") (pintype "bidirectional"))
    )
    (net (code "30") (name "3V3") (class "Default")
      (node (ref "2") (pin "7") (pinfunction "7_7") (pintype "passive"))
      (node (ref "2") (pin "8") (pinfunction "8_8") (pintype "passive"))
      (node (ref "C1") (pin "1") (pinfunction "1_1") (pintype "passive"))
      (node (ref "C2") (pin "2") (pinfunction "2_2") (pintype "passive"))
      (node (ref "C26") (pin "1") (pinfunction "1_1") (pintype "passive"))
      (node (ref "C7") (pin "2") (pinfunction "2_2") (pintype "passive"))
      (node (ref "DL1") (pin "2") (pinfunction "A_2") (pintype "passive"))
      (node (ref "DL2") (pin "2") (pinfunction "A_2") (pintype "passive"))
      (node (ref "R12") (pin "2") (pinfunction "2_2") (pintype "passive"))
      (node (ref "TP3") (pin "1") (pinfunction "1_1") (pintype "passive"))
      (node (ref "TP9") (pin "1") (pinfunction "1_1") (pintype "passive"))
      (node (ref "U1") (pin "1") (pinfunction "RESV_VDDIO_1") (pintype "passive"))
      (node (ref "U1") (pin "13") (pinfunction "VDD_13") (pintype "passive"))
      (node (ref "U1") (pin "22") (pinfunction "nCS_22") (pintype "passive"))
      (node (ref "U1") (pin "8") (pinfunction "VDDIO_8") (pintype "passive"))
      (node (ref "U3") (pin "5") (pinfunction "OUT_5") (pintype "power_in"))
      (node (ref "U7") (pin "6") (pinfunction "VCCB_6") (pintype "passive"))
      (node (ref "VR1") (pin "1") (pinfunction "1_1") (pintype "passive"))
      (node (ref "VR1") (pin "4") (pinfunction "1'_4") (pintype "passive"))
    )
    (net (code "31") (name "3V3_RADIO") (class "Default")
      (node (ref "C12") (pin "2") (pinfunction "2_2") (pintype "passive"))
      (node (ref "R10") (pin "2") (pinfunction "2_2") (pintype "passive"))
      (node (ref "TP11") (pin "1") (pinfunction "1_1") (pintype "passive"))
      (node (ref "U5") (pin "5") (pinfunction "OUT_5") (pintype "power_in"))
    )
    (net (code "32") (name "5V") (class "Default")
      (node (ref "C10") (pin "2") (pinfunction "2_2") (pintype "passive"))
      (node (ref "C11") (pin "2") (pinfunction "2_2") (pintype "passive"))
      (node (ref "C25") (pin "1") (pinfunction "1_1") (pintype "passive"))
      (node (ref "C6") (pin "2") (pinfunction "2_2") (pintype "passive"))
      (node (ref "H1") (pin "1") (pinfunction "1_1") (pintype "passive"))
      (node (ref "H3") (pin "1") (pinfunction "1_1") (pintype "passive"))
      (node (ref "L1") (pin "2") (pintype "passive"))
      (node (ref "R3") (pin "1") (pinfunction "1_1") (pintype "passive"))
      (node (ref "TP12") (pin "1") (pinfunction "1_1") (pintype "passive"))
      (node (ref "U3") (pin "1") (pinfunction "IN_1") (pintype "power_in"))
      (node (ref "U3") (pin "3") (pinfunction "EN_3") (pintype "input"))
      (node (ref "U4") (pin "5") (pinfunction "FB_5") (pintype "input"))
      (node (ref "U5") (pin "1") (pinfunction "IN_1") (pintype "power_in"))
      (node (ref "U5") (pin "3") (pinfunction "EN_3") (pintype "input"))
      (node (ref "U7") (pin "1") (pinfunction "VCCA_1") (pintype "passive"))
    )
    (net (code "33") (name "GND") (class "Default")
      (node (ref "1") (pin "5") (pinfunction "GND_5") (pintype "passive"))
      (node (ref "1") (pin "6") (pinfunction "SHLD_6") (pintype "passive"))
      (node (ref "2") (pin "5") (pinfunction "5_5") (pintype "passive"))
      (node (ref "2") (pin "6") (pinfunction "6_6") (pintype "passive"))
      (node (ref "C1") (pin "2") (pinfunction "2_2") (pintype "passive"))
      (node (ref "C10") (pin "1") (pinfunction "1_1") (pintype "passive"))
      (node (ref "C11") (pin "1") (pinfunction "1_1") (pintype "passive"))
      (node (ref "C12") (pin "1") (pinfunction "1_1") (pintype "passive"))
      (node (ref "C13") (pin "1") (pinfunction "1_1") (pintype "passive"))
      (node (ref "C14") (pin "1") (pinfunction "1_1") (pintype "passive"))
      (node (ref "C15") (pin "2") (pinfunction "2_2") (pintype "passive"))
      (node (ref "C16") (pin "1") (pinfunction "1_1") (pintype "passive"))
      (node (ref "C17") (pin "2") (pinfunction "2_2") (pintype "passive"))
      (node (ref "C18") (pin "1") (pinfunction "1_1") (pintype "passive"))
      (node (ref "C19") (pin "2") (pinfunction "2_2") (pintype "passive"))
      (node (ref "C2") (pin "1") (pinfunction "1_1") (pintype "passive"))
      (node (ref "C20") (pin "1") (pinfunction "1_1") (pintype "passive"))
      (node (ref "C21") (pin "2") (pinfunction "2_2") (pintype "passive"))
      (node (ref "C22") (pin "1") (pinfunction "1_1") (pintype "passive"))
      (node (ref "C24") (pin "1") (pinfunction "1_1") (pintype "passive"))
      (node (ref "C25") (pin "2") (pinfunction "2_2") (pintype "passive"))
      (node (ref "C26") (pin "2") (pinfunction "2_2") (pintype "passive"))
      (node (ref "C3") (pin "2") (pinfunction "2_2") (pintype "passive"))
      (node (ref "C4") (pin "1") (pinfunction "1_1") (pintype "passive"))
      (node (ref "C5") (pin "1") (pinfunction "1_1") (pintype "passive"))
      (node (ref "C6") (pin "1") (pinfunction "1_1") (pintype "passive"))
      (node (ref "C7") (pin "1") (pinfunction "1_1") (pintype "passive"))
      (node (ref "C9") (pin "1") (pinfunction "1_1") (pintype "passive"))
      (node (ref "D2") (pin "1") (pinfunction "A_1") (pintype "passive"))
      (node (ref "H2") (pin "1") (pinfunction "GND_1") (pintype "passive"))
      (node (ref "H2") (pin "3") (pinfunction "GND_3") (pintype "passive"))
      (node (ref "H3") (pin "3") (pinfunction "3_3") (pintype "passive"))
      (node (ref "Q1") (pin "2") (pinfunction "2_2") (pintype "passive"))
      (node (ref "R11") (pin "2") (pinfunction "2_2") (pintype "passive"))
      (node (ref "R14") (pin "2") (pinfunction "2_2") (pintype "passive"))
      (node (ref "R2") (pin "1") (pinfunction "1_1") (pintype "passive"))
      (node (ref "R7") (pin "1") (pinfunction "1_1") (pintype "passive"))
      (node (ref "S1") (pin "2") (pintype "passive"))
      (node (ref "S2") (pin "2") (pintype "passive"))
      (node (ref "S3") (pin "5") (pinfunction "B4_5") (pintype "passive"))
      (node (ref "S3") (pin "6") (pinfunction "B3_6") (pintype "passive"))
      (node (ref "S3") (pin "7") (pinfunction "B2_7") (pintype "passive"))
      (node (ref "S3") (pin "8") (pinfunction "B1_8") (pintype "passive"))
      (node (ref "S4") (pin "2") (pintype "passive"))
      (node (ref "TP5") (pin "1") (pinfunction "1_1") (pintype "passive"))
      (node (ref "TP6") (pin "1") (pinfunction "1_1") (pintype "passive"))
      (node (ref "TP7") (pin "1") (pinfunction "1_1") (pintype "passive"))
      (node (ref "TP8") (pin "1") (pinfunction "1_1") (pintype "passive"))
      (node (ref "U1") (pin "11") (pinfunction "FSYNC_11") (pintype "passive"))
      (node (ref "U1") (pin "18") (pinfunction "GND_18") (pintype "passive"))
      (node (ref "U1") (pin "20") (pinfunction "RESV_GND_20") (pintype "passive"))
      (node (ref "U1") (pin "9") (pinfunction "AD0/SDO_9") (pintype "passive"))
      (node (ref "U2") (pin "17") (pinfunction "GND_17") (pintype "power_in"))
      (node (ref "U2") (pin "2") (pinfunction "GND_2") (pintype "power_in"))
      (node (ref "U2") (pin "46") (pinfunction "GND_46") (pintype "power_in"))
      (node (ref "U2") (pin "60") (pinfunction "GND_60") (pintype "power_in"))
      (node (ref "U3") (pin "2") (pinfunction "GND_2") (pintype "power_in"))
      (node (ref "U4") (pin "7") (pinfunction "GND_7") (pintype "power_in"))
      (node (ref "U4") (pin "EPAD") (pinfunction "EPAD_EPAD") (pintype "passive"))
      (node (ref "U5") (pin "2") (pinfunction "GND_2") (pintype "power_in"))
      (node (ref "U6") (pin "2") (pinfunction "GND_2") (pintype "passive"))
      (node (ref "U7") (pin "2") (pinfunction "GND_2") (pintype "passive"))
      (node (ref "U7") (pin "5") (pinfunction "DIR_5") (pintype "passive"))
      (node (ref "VR1") (pin "3") (pinfunction "3_3") (pintype "passive"))
      (node (ref "VR1") (pin "6") (pinfunction "3'_6") (pintype "passive"))
      (node (ref "VR1") (pin "8") (pinfunction "8_8") (pintype "passive"))
      (node (ref "VR1") (pin "9") (pinfunction "9_9") (pintype "passive"))
    )
    (net (code "34") (name "Net-(C23-Pad2)") (class "Default")
      (node (ref "C23") (pin "2") (pinfunction "2_2") (pintype "passive"))
      (node (ref "R14") (pin "1") (pinfunction "1_1") (pintype "passive"))
    )
    (net (code "35") (name "Net-(D1-A)") (class "Default")
      (node (ref "D1") (pin "1") (pinfunction "A_1") (pintype "passive"))
      (node (ref "H1") (pin "2") (pinfunction "2_2") (pintype "passive"))
      (node (ref "Q1") (pin "3") (pinfunction "3_3") (pintype "passive"))
    )
    (net (code "36") (name "Net-(D1-K)") (class "Default")
      (node (ref "D1") (pin "3") (pinfunction "K_3") (pintype "passive"))
      (node (ref "R3") (pin "2") (pinfunction "2_2") (pintype "passive"))
    )
    (net (code "37") (name "Net-(D2-K)") (class "Default")
      (node (ref "C8") (pin "2") (pinfunction "2_2") (pintype "passive"))
      (node (ref "D2") (pin "2") (pinfunction "K_2") (pintype "passive"))
      (node (ref "L1") (pin "1") (pintype "passive"))
      (node (ref "U4") (pin "8") (pinfunction "SW_8") (pintype "output"))
    )
    (net (code "38") (name "Net-(DL1-K)") (class "Default")
      (node (ref "DL1") (pin "1") (pinfunction "K_1") (pintype "passive"))
      (node (ref "R13") (pin "1") (pinfunction "1_1") (pintype "passive"))
    )
    (net (code "39") (name "Net-(DL2-K)") (class "Default")
      (node (ref "DL2") (pin "1") (pinfunction "K_1") (pintype "passive"))
      (node (ref "R15") (pin "1") (pinfunction "1_1") (pintype "passive"))
    )
    (net (code "40") (name "Net-(F1-Pad1)") (class "Default")
      (node (ref "F1") (pin "1") (pinfunction "1_1") (pintype "passive"))
      (node (ref "Q2") (pin "3") (pinfunction "3_3") (pintype "passive"))
    )
    (net (code "41") (name "Net-(Q1-Pad1)") (class "Default")
      (node (ref "Q1") (pin "1") (pinfunction "1_1") (pintype "passive"))
      (node (ref "R6") (pin "1") (pinfunction "1_1") (pintype "passive"))
    )
    (net (code "42") (name "Net-(Q2-Pad1)") (class "Default")
      (node (ref "Q2") (pin "1") (pinfunction "1_1") (pintype "passive"))
      (node (ref "R7") (pin "2") (pinfunction "2_2") (pintype "passive"))
    )
    (net (code "43") (name "Net-(U1-REGOUT)") (class "Default")
      (node (ref "C3") (pin "1") (pinfunction "1_1") (pintype "passive"))
      (node (ref "U1") (pin "10") (pinfunction "REGOUT_10") (pintype "passive"))
    )
    (net (code "44") (name "Net-(U2A-DDM{slash}PB10)") (class "Default")
      (node (ref "R5") (pin "2") (pinfunction "2_2") (pintype "passive"))
      (node (ref "U2") (pin "56") (pinfunction "DDM/PB10_56") (pintype "bidirectional"))
    )
    (net (code "45") (name "Net-(U2A-DDP{slash}PB11)") (class "Default")
      (node (ref "R4") (pin "2") (pinfunction "2_2") (pintype "passive"))
      (node (ref "U2") (pin "57") (pinfunction "DDP/PB11_57") (pintype "bidirectional"))
    )
    (net (code "46") (name "Net-(U2A-ERASE{slash}PB12)") (class "Default")
      (node (ref "TP4") (pin "1") (pinfunction "1_1") (pintype "passive"))
      (node (ref "U2") (pin "55") (pinfunction "ERASE/PB12_55") (pintype "bidirectional"))
    )
    (net (code "47") (name "Net-(U2A-XIN{slash}PGMCK{slash}PB9)") (class "Default")
      (node (ref "C4") (pin "2") (pinfunction "2_2") (pintype "passive"))
      (node (ref "U2") (pin "62") (pinfunction "XIN/PGMCK/PB9_62") (pintype "bidirectional"))
      (node (ref "Y1") (pin "3") (pinfunction "OSC2_3") (pintype "passive"))
    )
    (net (code "48") (name "Net-(U2A-XOUT{slash}PB8)") (class "Default")
      (node (ref "C5") (pin "2") (pinfunction "2_2") (pintype "passive"))
      (node (ref "U2") (pin "61") (pinfunction "XOUT/PB8_61") (pintype "bidirectional"))
      (node (ref "Y1") (pin "1") (pinfunction "OSC1_1") (pintype "passive"))
    )
    (net (code "49") (name "Net-(U2B-ADVREF)") (class "Default")
      (node (ref "C14") (pin "2") (pinfunction "2_2") (pintype "passive"))
      (node (ref "C16") (pin "2") (pinfunction "2_2") (pintype "passive"))
      (node (ref "C18") (pin "2") (pinfunction "2_2") (pintype "passive"))
      (node (ref "C20") (pin "2") (pinfunction "2_2") (pintype "passive"))
      (node (ref "C22") (pin "2") (pinfunction "2_2") (pintype "passive"))
      (node (ref "R12") (pin "1") (pinfunction "1_1") (pintype "passive"))
      (node (ref "U2") (pin "1") (pinfunction "ADVREF_1") (pintype "input"))
      (node (ref "U2") (pin "18") (pinfunction "VDDIO_18") (pintype "power_in"))
      (node (ref "U2") (pin "45") (pinfunction "VDDIO_45") (pintype "power_in"))
      (node (ref "U2") (pin "58") (pinfunction "VDDIO_58") (pintype "power_in"))
      (node (ref "U2") (pin "7") (pinfunction "VDDIN_7") (pintype "power_in"))
    )
    (net (code "50") (name "Net-(U2B-VDDOUT)") (class "Default")
      (node (ref "C15") (pin "1") (pinfunction "1_1") (pintype "passive"))
      (node (ref "C17") (pin "1") (pinfunction "1_1") (pintype "passive"))
      (node (ref "C19") (pin "1") (pinfunction "1_1") (pintype "passive"))
      (node (ref "C21") (pin "1") (pinfunction "1_1") (pintype "passive"))
      (node (ref "L2") (pin "2") (pinfunction "2_2") (pintype "passive"))
      (node (ref "U2") (pin "12") (pinfunction "VDDCORE_12") (pintype "power_in"))
      (node (ref "U2") (pin "24") (pinfunction "VDDCORE_24") (pintype "power_in"))
      (node (ref "U2") (pin "54") (pinfunction "VDDCORE_54") (pintype "power_in"))
      (node (ref "U2") (pin "8") (pinfunction "VDDOUT_8") (pintype "power_in"))
    )
    (net (code "51") (name "Net-(U2B-VDDPLL)") (class "Default")
      (node (ref "C23") (pin "1") (pinfunction "1_1") (pintype "passive"))
      (node (ref "C24") (pin "2") (pinfunction "2_2") (pintype "passive"))
      (node (ref "L2") (pin "1") (pinfunction "1_1") (pintype "passive"))
      (node (ref "U2") (pin "64") (pinfunction "VDDPLL_64") (pintype "power_in"))
    )
    (net (code "52") (name "Net-(U4-BST)") (class "Default")
      (node (ref "C8") (pin "1") (pinfunction "1_1") (pintype "passive"))
      (node (ref "U4") (pin "1") (pinfunction "BST_1") (pintype "passive"))
    )
    (net (code "53") (name "Net-(U4-EN)") (class "Default")
      (node (ref "R9") (pin "1") (pinfunction "1_1") (pintype "passive"))
      (node (ref "U4") (pin "3") (pinfunction "EN_3") (pintype "output"))
    )
    (net (code "54") (name "Net-(U6-VCC)") (class "Default")
      (node (ref "C13") (pin "2") (pinfunction "2_2") (pintype "passive"))
      (node (ref "R10") (pin "1") (pinfunction "1_1") (pintype "passive"))
      (node (ref "U6") (pin "1") (pinfunction "VCC_1") (pintype "passive"))
    )
    (net (code "55") (name "VBUS") (class "Default")
      (node (ref "1") (pin "1") (pinfunction "VBUS_1") (pintype "power_in"))
      (node (ref "R1") (pin "2") (pinfunction "2_2") (pintype "passive"))
    )
    (net (code "56") (name "V_BATT") (class "Default")
      (node (ref "F1") (pin "2") (pinfunction "2_2") (pintype "passive"))
      (node (ref "H2") (pin "2") (pinfunction "VBATT_2") (pintype "passive"))
    )
    (net (code "57") (name "V_BATT_FUSED") (class "Default")
      (node (ref "C9") (pin "2") (pinfunction "2_2") (pintype "passive"))
      (node (ref "Q2") (pin "2") (pinfunction "2_2") (pintype "passive"))
      (node (ref "R8") (pin "1") (pinfunction "1_1") (pintype "passive"))
      (node (ref "R9") (pin "2") (pinfunction "2_2") (pintype "passive"))
      (node (ref "TP10") (pin "1") (pinfunction "1_1") (pintype "passive"))
      (node (ref "U4") (pin "2") (pinfunction "VIN_2") (pintype "input"))
      (node (ref "U4") (pin "4") (pinfunction "PGOOD_4") (pintype "output"))
    )
    (net (code "58") (name "unconnected-(1-ID-Pad4)") (class "Default")
      (node (ref "1") (pin "4") (pinfunction "ID_4") (pintype "power_in"))
    )
    (net (code "59") (name "unconnected-(2-Pad3)") (class "Default")
      (node (ref "2") (pin "3") (pinfunction "3_3") (pintype "passive+no_connect"))
    )
    (net (code "60") (name "unconnected-(2-Pad9)") (class "Default")
      (node (ref "2") (pin "9") (pinfunction "9_9") (pintype "passive+no_connect"))
    )
    (net (code "61") (name "unconnected-(2-Pad10)") (class "Default")
      (node (ref "2") (pin "10") (pinfunction "10_10") (pintype "passive+no_connect"))
    )
    (net (code "62") (name "unconnected-(U1-AUX_CL-Pad7)") (class "Default")
      (node (ref "U1") (pin "7") (pinfunction "AUX_CL_7") (pintype "passive"))
    )
    (net (code "63") (name "unconnected-(U1-AUX_DA-Pad21)") (class "Default")
      (node (ref "U1") (pin "21") (pinfunction "AUX_DA_21") (pintype "passive"))
    )
    (net (code "64") (name "unconnected-(U1-INT-Pad12)") (class "Default")
      (node (ref "U1") (pin "12") (pinfunction "INT_12") (pintype "passive"))
    )
    (net (code "65") (name "unconnected-(U2A-JTAGSEL-Pad50)") (class "Default")
      (node (ref "U2") (pin "50") (pinfunction "JTAGSEL_50") (pintype "input+no_connect"))
    )
    (net (code "66") (name "unconnected-(U2A-PA4{slash}PGMNCMD{slash}TWCK0-Pad36)") (class "Default")
      (node (ref "U2") (pin "36") (pinfunction "PA4/PGMNCMD/TWCK0_36") (pintype "bidirectional"))
    )
    (net (code "67") (name "unconnected-(U2A-PA5{slash}PGMRDY-Pad35)") (class "Default")
      (node (ref "U2") (pin "35") (pinfunction "PA5/PGMRDY_35") (pintype "bidirectional"))
    )
    (net (code "68") (name "unconnected-(U2A-PA6{slash}PGMNOE-Pad34)") (class "Default")
      (node (ref "U2") (pin "34") (pinfunction "PA6/PGMNOE_34") (pintype "bidirectional"))
    )
    (net (code "69") (name "unconnected-(U2A-PA7{slash}XIN32{slash}PGMNVALID-Pad32)") (class "Default")
      (node (ref "U2") (pin "32") (pinfunction "PA7/XIN32/PGMNVALID_32") (pintype "bidirectional"))
    )
    (net (code "70") (name "unconnected-(U2A-PA8{slash}XOUT32{slash}PGMM0-Pad31)") (class "Default")
      (node (ref "U2") (pin "31") (pinfunction "PA8/XOUT32/PGMM0_31") (pintype "bidirectional"))
    )
    (net (code "71") (name "unconnected-(U2A-PA16{slash}PGMD4-Pad19)") (class "Default")
      (node (ref "U2") (pin "19") (pinfunction "PA16/PGMD4_19") (pintype "bidirectional"))
    )
    (net (code "72") (name "unconnected-(U2A-PA17{slash}PGMD5{slash}AD0-Pad9)") (class "Default")
      (node (ref "U2") (pin "9") (pinfunction "PA17/PGMD5/AD0_9") (pintype "bidirectional"))
    )
    (net (code "73") (name "unconnected-(U2A-PA18{slash}PGMD6{slash}AD1-Pad10)") (class "Default")
      (node (ref "U2") (pin "10") (pinfunction "PA18/PGMD6/AD1_10") (pintype "bidirectional"))
    )
    (net (code "74") (name "unconnected-(U2A-PA24{slash}PGMD12-Pad23)") (class "Default")
      (node (ref "U2") (pin "23") (pinfunction "PA24/PGMD12_23") (pintype "bidirectional"))
    )
    (net (code "75") (name "unconnected-(U2A-PA25{slash}PGMD13-Pad25)") (class "Default")
      (node (ref "U2") (pin "25") (pinfunction "PA25/PGMD13_25") (pintype "bidirectional"))
    )
    (net (code "76") (name "unconnected-(U2A-PA26{slash}PGMD14-Pad26)") (class "Default")
      (node (ref "U2") (pin "26") (pinfunction "PA26/PGMD14_26") (pintype "bidirectional"))
    )
    (net (code "77") (name "unconnected-(U2A-PA27{slash}PGMD15-Pad37)") (class "Default")
      (node (ref "U2") (pin "37") (pinfunction "PA27/PGMD15_37") (pintype "bidirectional"))
    )
    (net (code "78") (name "unconnected-(U2A-PA28-Pad38)") (class "Default")
      (node (ref "U2") (pin "38") (pinfunction "PA28_38") (pintype "bidirectional"))
    )
    (net (code "79") (name "unconnected-(U2A-PA30-Pad42)") (class "Default")
      (node (ref "U2") (pin "42") (pinfunction "PA30_42") (pintype "bidirectional"))
    )
    (net (code "80") (name "unconnected-(U2A-PB3{slash}AD7-Pad6)") (class "Default")
      (node (ref "U2") (pin "6") (pinfunction "PB3/AD7_6") (pintype "bidirectional"))
    )
    (net (code "81") (name "unconnected-(U2A-PB13{slash}DAC0-Pad59)") (class "Default")
      (node (ref "U2") (pin "59") (pinfunction "PB13/DAC0_59") (pintype "bidirectional"))
    )
    (net (code "82") (name "unconnected-(U2A-PB14{slash}DAC1-Pad63)") (class "Default")
      (node (ref "U2") (pin "63") (pinfunction "PB14/DAC1_63") (pintype "bidirectional"))
    )
    (net (code "83") (name "unconnected-(U2A-TST-Pad40)") (class "Default")
      (node (ref "U2") (pin "40") (pinfunction "TST_40") (pintype "input+no_connect"))
    )
    (net (code "84") (name "unconnected-(U3-BYP-Pad4)") (class "Default")
      (node (ref "U3") (pin "4") (pinfunction "BYP_4") (pintype "passive"))
    )
    (net (code "85") (name "unconnected-(U4-NC-Pad6)") (class "Default")
      (node (ref "U4") (pin "6") (pinfunction "NC_6") (pintype "passive"))
    )
    (net (code "86") (name "unconnected-(U5-BYP-Pad4)") (class "Default")
      (node (ref "U5") (pin "4") (pinfunction "BYP_4") (pintype "passive"))
    )
  )
)
